# DMX-Card.net
KiCad netlist of a schematic drawn in EAGLE
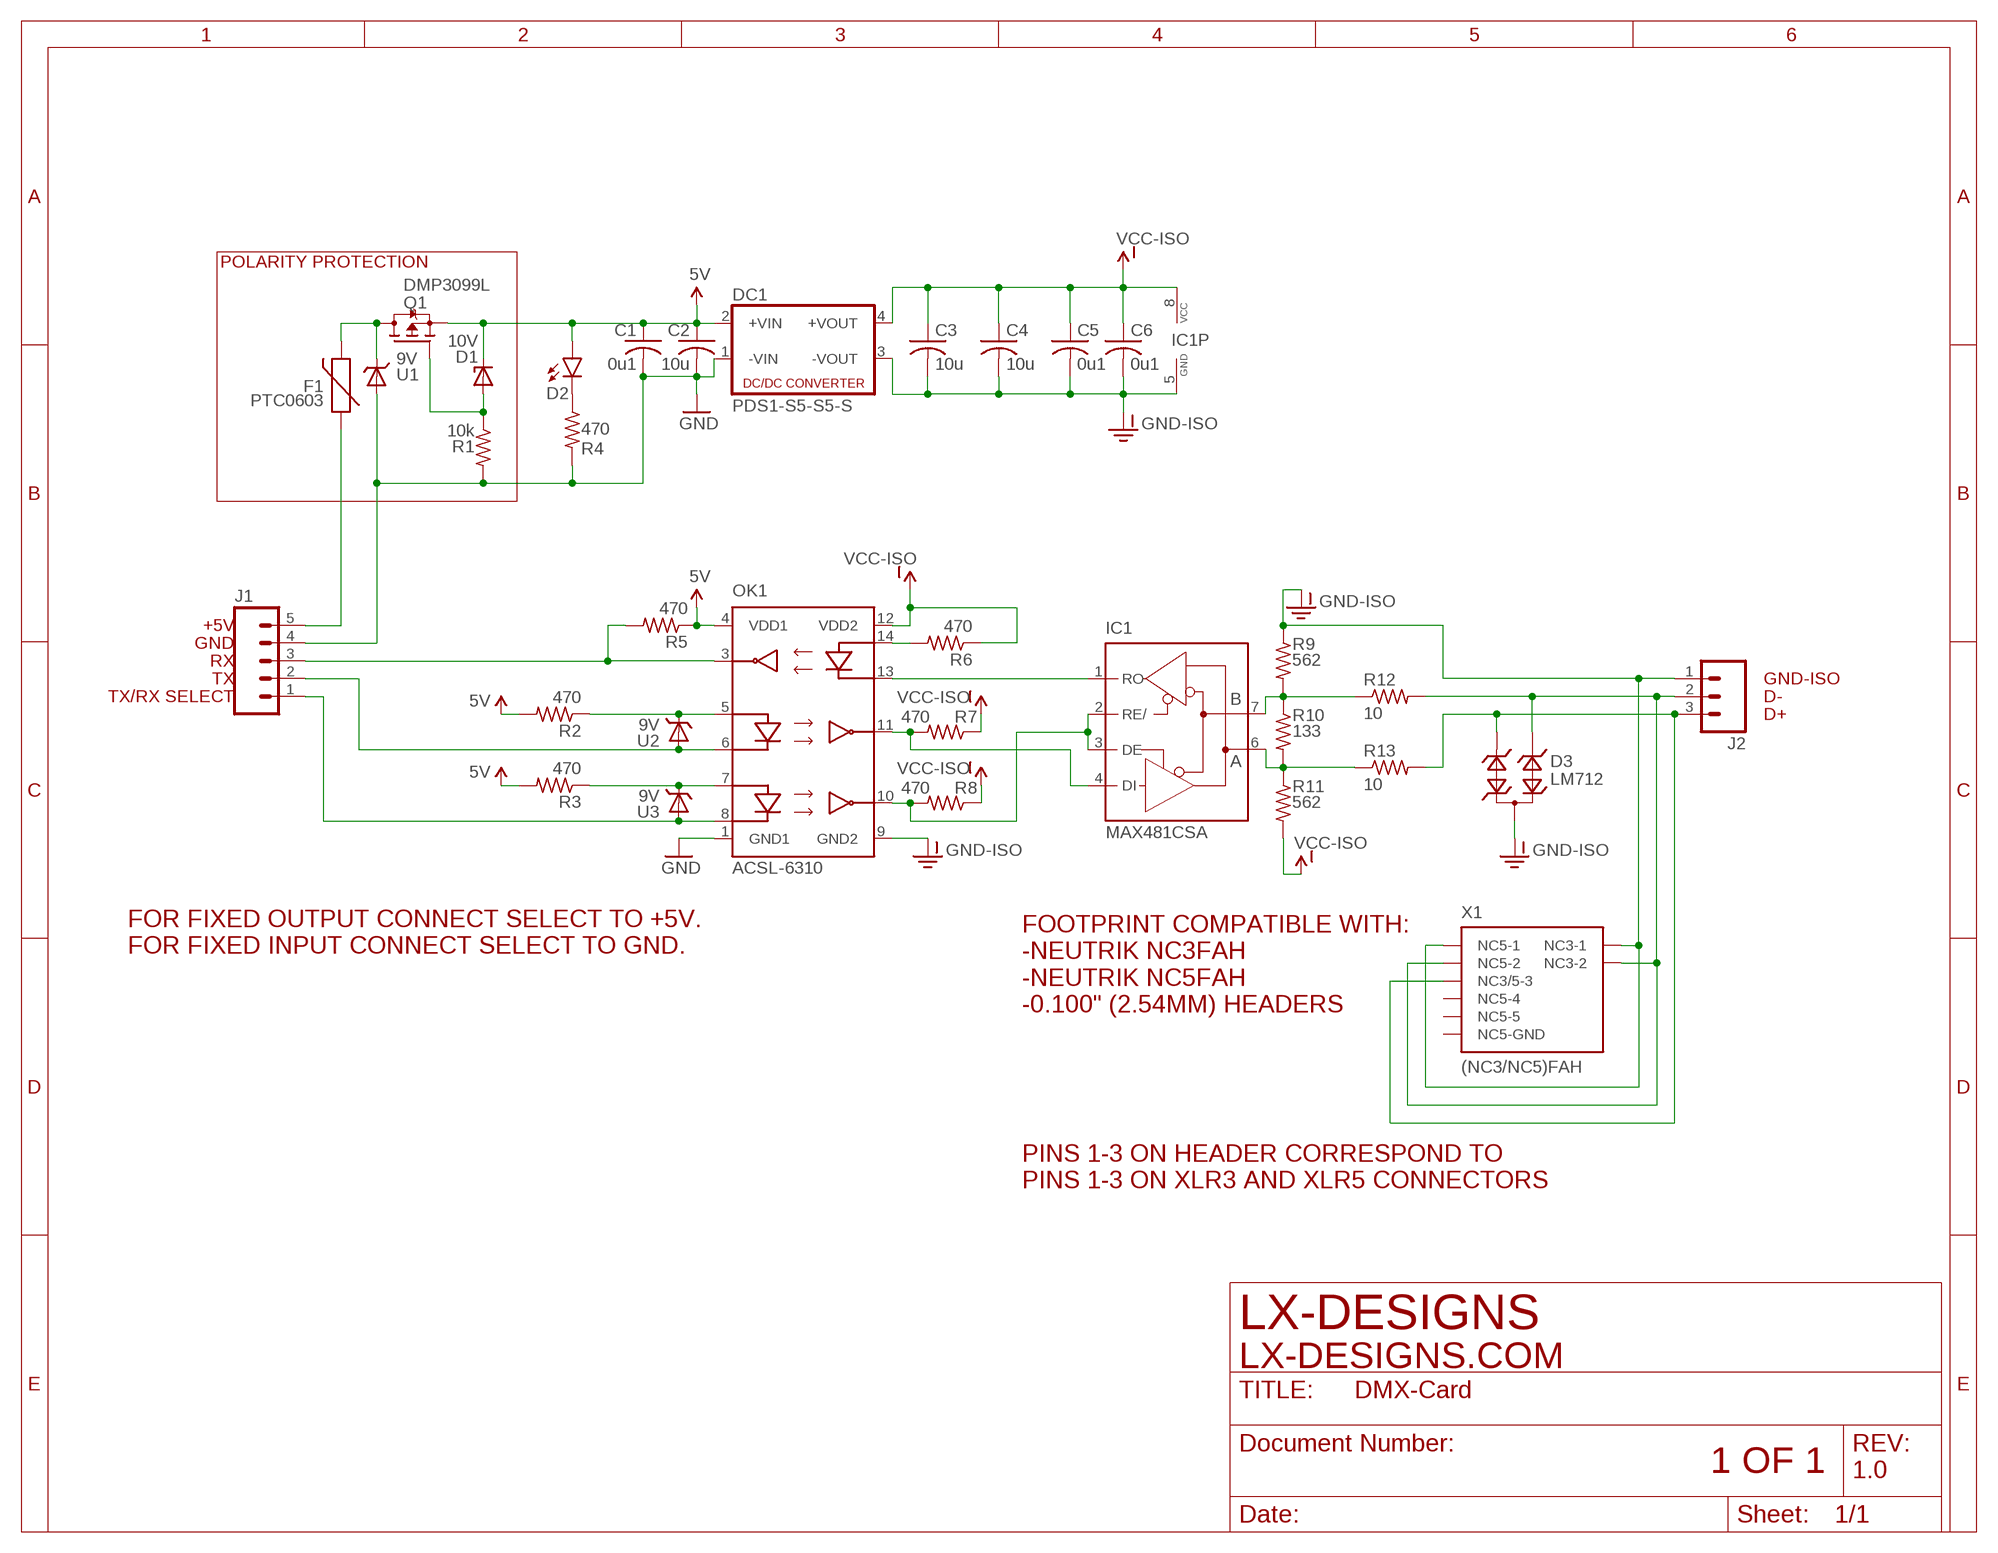
[diagram p0: schematic, sheet 1]

(export (version "E")
  (design (tool "Eeschema 10.0.6"))
  (components
    (comp (ref "C1")
      (value "0u1")
      (footprint "eagle-import:C0603K")
      (libsource (lib "eagle-import") (part "C-USC0603K"))
    )
    (comp (ref "C2")
      (value "10u")
      (footprint "eagle-import:C0603K")
      (libsource (lib "eagle-import") (part "C-USC0603K"))
    )
    (comp (ref "C3")
      (value "10u")
      (footprint "eagle-import:C0603K")
      (libsource (lib "eagle-import") (part "C-USC0603K"))
    )
    (comp (ref "C4")
      (value "10u")
      (footprint "eagle-import:C0603K")
      (libsource (lib "eagle-import") (part "C-USC0603K"))
    )
    (comp (ref "C5")
      (value "0u1")
      (footprint "eagle-import:C0603K")
      (libsource (lib "eagle-import") (part "C-USC0603K"))
    )
    (comp (ref "C6")
      (value "0u1")
      (footprint "eagle-import:C0603K")
      (libsource (lib "eagle-import") (part "C-USC0603K"))
    )
    (comp (ref "D1")
      (value "10V")
      (footprint "eagle-import:SOD323")
      (libsource (lib "eagle-import") (part "ZENER-DIODESOD-323"))
    )
    (comp (ref "D2")
      (value "LED0603")
      (footprint "eagle-import:LED-0603")
      (libsource (lib "eagle-import") (part "LED0603"))
    )
    (comp (ref "D3")
      (value "LM712")
      (footprint "eagle-import:SOT23")
      (libsource (lib "eagle-import") (part "CDSOT23-SM712SOT23-STANDARD"))
    )
    (comp (ref "DC1")
      (value "PDS1-S5-S5-S")
      (footprint "eagle-import:4SIL")
      (libsource (lib "eagle-import") (part "VA-?S0505"))
    )
    (comp (ref "F1")
      (value "PTC0603")
      (footprint "eagle-import:0603")
      (libsource (lib "eagle-import") (part "PTC0603"))
    )
    (comp (ref "IC1")
      (value "MAX481CSA")
      (footprint "eagle-import:SO08")
      (fields (field (name "MF") "MAXIM"))
      (libsource (lib "eagle-import") (part "MAX481CSA"))
    )
    (comp (ref "J1")
      (value "M05NO_SILK")
      (footprint "eagle-import:1X05_NO_SILK")
      (libsource (lib "eagle-import") (part "M05NO_SILK"))
    )
    (comp (ref "J2")
      (value "M031X03_NO_SILK")
      (footprint "eagle-import:1X03_NO_SILK")
      (libsource (lib "eagle-import") (part "M031X03_NO_SILK"))
    )
    (comp (ref "OK1")
      (value "ACSL-6310")
      (footprint "eagle-import:SO-16")
      (libsource (lib "eagle-import") (part "ACSL-60"))
    )
    (comp (ref "Q1")
      (value "DMP3099L")
      (footprint "eagle-import:SOT23")
      (libsource (lib "eagle-import") (part "BSA223SPSOT23"))
    )
    (comp (ref "R1")
      (value "10k")
      (footprint "eagle-import:R0603")
      (libsource (lib "eagle-import") (part "R-US_R0603"))
    )
    (comp (ref "R2")
      (value "470")
      (footprint "eagle-import:R0603")
      (libsource (lib "eagle-import") (part "R-US_R0603"))
    )
    (comp (ref "R3")
      (value "470")
      (footprint "eagle-import:R0603")
      (libsource (lib "eagle-import") (part "R-US_R0603"))
    )
    (comp (ref "R4")
      (value "470")
      (footprint "eagle-import:R0603")
      (libsource (lib "eagle-import") (part "R-US_R0603"))
    )
    (comp (ref "R5")
      (value "470")
      (footprint "eagle-import:R0603")
      (libsource (lib "eagle-import") (part "R-US_R0603"))
    )
    (comp (ref "R6")
      (value "470")
      (footprint "eagle-import:R0603")
      (libsource (lib "eagle-import") (part "R-US_R0603"))
    )
    (comp (ref "R7")
      (value "470")
      (footprint "eagle-import:R0603")
      (libsource (lib "eagle-import") (part "R-US_R0603"))
    )
    (comp (ref "R8")
      (value "470")
      (footprint "eagle-import:R0603")
      (libsource (lib "eagle-import") (part "R-US_R0603"))
    )
    (comp (ref "R9")
      (value "562")
      (footprint "eagle-import:R0603")
      (libsource (lib "eagle-import") (part "R-US_R0603"))
    )
    (comp (ref "R10")
      (value "133")
      (footprint "eagle-import:R0603")
      (libsource (lib "eagle-import") (part "R-US_R0603"))
    )
    (comp (ref "R11")
      (value "562")
      (footprint "eagle-import:R0603")
      (libsource (lib "eagle-import") (part "R-US_R0603"))
    )
    (comp (ref "R12")
      (value "10")
      (footprint "eagle-import:R0603")
      (libsource (lib "eagle-import") (part "R-US_R0603"))
    )
    (comp (ref "R13")
      (value "10")
      (footprint "eagle-import:R0603")
      (libsource (lib "eagle-import") (part "R-US_R0603"))
    )
    (comp (ref "U1")
      (value "9V")
      (footprint "eagle-import:SOD323-NOSILK")
      (libsource (lib "eagle-import") (part "TVS-DIODESOD323-NOSILK"))
    )
    (comp (ref "U2")
      (value "9V")
      (footprint "eagle-import:SOD323-NOSILK")
      (libsource (lib "eagle-import") (part "TVS-DIODESOD323-NOSILK"))
    )
    (comp (ref "U3")
      (value "9V")
      (footprint "eagle-import:SOD323-NOSILK")
      (libsource (lib "eagle-import") (part "TVS-DIODESOD323-NOSILK"))
    )
    (comp (ref "X1")
      (value "(NC3/NC5)FAH")
      (footprint "eagle-import:NC3FAH-NC5FAH-NOSILK")
      (libsource (lib "eagle-import") (part "CUSTOMNC3FAH-NC3MAH-NOSILK"))
    )
  )
  (nets
    (net (code "1") (name "5V") (class "Default")
      (node (ref "C1") (pin "1") (pinfunction "1_1") (pintype "passive"))
      (node (ref "C2") (pin "1") (pinfunction "1_1") (pintype "passive"))
      (node (ref "D1") (pin "C") (pinfunction "C_C") (pintype "passive"))
      (node (ref "D2") (pin "A") (pinfunction "A_A") (pintype "passive"))
      (node (ref "DC1") (pin "2") (pinfunction "+VIN_2") (pintype "passive"))
      (node (ref "OK1") (pin "4") (pinfunction "VDD1_4") (pintype "power_in"))
      (node (ref "Q1") (pin "2") (pinfunction "S_2") (pintype "passive"))
      (node (ref "R2") (pin "2") (pinfunction "2_2") (pintype "passive"))
      (node (ref "R3") (pin "2") (pinfunction "2_2") (pintype "passive"))
      (node (ref "R5") (pin "1") (pinfunction "1_1") (pintype "passive"))
    )
    (net (code "2") (name "GND") (class "Default")
      (node (ref "C1") (pin "2") (pinfunction "2_2") (pintype "passive"))
      (node (ref "C2") (pin "2") (pinfunction "2_2") (pintype "passive"))
      (node (ref "DC1") (pin "1") (pinfunction "-VIN_1") (pintype "passive"))
      (node (ref "J1") (pin "4") (pinfunction "4_4") (pintype "passive"))
      (node (ref "OK1") (pin "1") (pinfunction "GND1_1") (pintype "bidirectional"))
      (node (ref "R1") (pin "2") (pinfunction "2_2") (pintype "passive"))
      (node (ref "R4") (pin "2") (pinfunction "2_2") (pintype "passive"))
      (node (ref "U1") (pin "A") (pinfunction "A_A") (pintype "passive"))
    )
    (net (code "3") (name "GND-ISO") (class "Default")
      (node (ref "C3") (pin "2") (pinfunction "2_2") (pintype "passive"))
      (node (ref "C4") (pin "2") (pinfunction "2_2") (pintype "passive"))
      (node (ref "C5") (pin "2") (pinfunction "2_2") (pintype "passive"))
      (node (ref "C6") (pin "2") (pinfunction "2_2") (pintype "passive"))
      (node (ref "D3") (pin "3") (pinfunction "3_3") (pintype "passive"))
      (node (ref "DC1") (pin "3") (pinfunction "-VOUT_3") (pintype "passive"))
      (node (ref "IC1") (pin "5") (pinfunction "GND_5") (pintype "power_in"))
      (node (ref "J2") (pin "1") (pinfunction "1_1") (pintype "passive"))
      (node (ref "OK1") (pin "9") (pinfunction "GND2_9") (pintype "power_in"))
      (node (ref "R9") (pin "1") (pinfunction "1_1") (pintype "passive"))
      (node (ref "X1") (pin "NC3-1") (pinfunction "NC3-1_NC3-1") (pintype "bidirectional"))
      (node (ref "X1") (pin "NC5-1") (pinfunction "NC5-1_NC5-1") (pintype "bidirectional"))
    )
    (net (code "4") (name "Net-(D2-PadC)") (class "Default")
      (node (ref "D2") (pin "C") (pinfunction "C_C") (pintype "passive"))
      (node (ref "R4") (pin "1") (pinfunction "1_1") (pintype "passive"))
    )
    (net (code "5") (name "Net-(D3-Pad1)") (class "Default")
      (node (ref "D3") (pin "1") (pinfunction "1_1") (pintype "passive"))
      (node (ref "J2") (pin "2") (pinfunction "2_2") (pintype "passive"))
      (node (ref "R12") (pin "2") (pinfunction "2_2") (pintype "passive"))
      (node (ref "X1") (pin "NC3-2") (pinfunction "NC3-2_NC3-2") (pintype "bidirectional"))
      (node (ref "X1") (pin "NC5-2") (pinfunction "NC5-2_NC5-2") (pintype "bidirectional"))
    )
    (net (code "6") (name "Net-(F1-Pad1)") (class "Default")
      (node (ref "F1") (pin "1") (pinfunction "1_1") (pintype "bidirectional"))
      (node (ref "J1") (pin "5") (pinfunction "5_5") (pintype "passive"))
    )
    (net (code "7") (name "Net-(IC1A-A)") (class "Default")
      (node (ref "IC1") (pin "6") (pinfunction "A_6") (pintype "passive"))
      (node (ref "R10") (pin "2") (pinfunction "2_2") (pintype "passive"))
      (node (ref "R11") (pin "1") (pinfunction "1_1") (pintype "passive"))
      (node (ref "R13") (pin "1") (pinfunction "1_1") (pintype "passive"))
    )
    (net (code "8") (name "Net-(IC1A-B)") (class "Default")
      (node (ref "IC1") (pin "7") (pinfunction "B_7") (pintype "passive"))
      (node (ref "R10") (pin "1") (pinfunction "1_1") (pintype "passive"))
      (node (ref "R12") (pin "1") (pinfunction "1_1") (pintype "passive"))
      (node (ref "R9") (pin "2") (pinfunction "2_2") (pintype "passive"))
    )
    (net (code "9") (name "Net-(IC1A-DE)") (class "Default")
      (node (ref "IC1") (pin "2") (pinfunction "RE/_2") (pintype "input"))
      (node (ref "IC1") (pin "3") (pinfunction "DE_3") (pintype "input"))
      (node (ref "OK1") (pin "10") (pinfunction "VO2_10") (pintype "output"))
      (node (ref "R8") (pin "2") (pinfunction "2_2") (pintype "passive"))
    )
    (net (code "10") (name "Net-(IC1A-DI)") (class "Default")
      (node (ref "IC1") (pin "4") (pinfunction "DI_4") (pintype "input"))
      (node (ref "OK1") (pin "11") (pinfunction "VO1_11") (pintype "output"))
      (node (ref "R7") (pin "2") (pinfunction "2_2") (pintype "passive"))
    )
    (net (code "11") (name "Net-(IC1A-RO)") (class "Default")
      (node (ref "IC1") (pin "1") (pinfunction "RO_1") (pintype "output"))
      (node (ref "OK1") (pin "13") (pinfunction "C3_13") (pintype "output"))
    )
    (net (code "12") (name "Net-(OK1-A1)") (class "Default")
      (node (ref "OK1") (pin "5") (pinfunction "A1_5") (pintype "input"))
      (node (ref "R2") (pin "1") (pinfunction "1_1") (pintype "passive"))
      (node (ref "U2") (pin "C") (pinfunction "C_C") (pintype "passive"))
    )
    (net (code "13") (name "Net-(OK1-A2)") (class "Default")
      (node (ref "OK1") (pin "7") (pinfunction "A2_7") (pintype "input"))
      (node (ref "R3") (pin "1") (pinfunction "1_1") (pintype "passive"))
      (node (ref "U3") (pin "C") (pinfunction "C_C") (pintype "passive"))
    )
    (net (code "14") (name "Net-(OK1-A3)") (class "Default")
      (node (ref "OK1") (pin "14") (pinfunction "A3_14") (pintype "input"))
      (node (ref "R6") (pin "2") (pinfunction "2_2") (pintype "passive"))
    )
    (net (code "15") (name "Net-(OK1-C1)") (class "Default")
      (node (ref "J1") (pin "2") (pinfunction "2_2") (pintype "passive"))
      (node (ref "OK1") (pin "6") (pinfunction "C1_6") (pintype "output"))
      (node (ref "U2") (pin "A") (pinfunction "A_A") (pintype "passive"))
    )
    (net (code "16") (name "Net-(OK1-C2)") (class "Default")
      (node (ref "J1") (pin "1") (pinfunction "1_1") (pintype "passive"))
      (node (ref "OK1") (pin "8") (pinfunction "C2_8") (pintype "output"))
      (node (ref "U3") (pin "A") (pinfunction "A_A") (pintype "passive"))
    )
    (net (code "17") (name "Net-(OK1-V03)") (class "Default")
      (node (ref "J1") (pin "3") (pinfunction "3_3") (pintype "passive"))
      (node (ref "OK1") (pin "3") (pinfunction "V03_3") (pintype "output"))
      (node (ref "R5") (pin "2") (pinfunction "2_2") (pintype "passive"))
    )
    (net (code "18") (name "Net-(Q1-D)") (class "Default")
      (node (ref "F1") (pin "2") (pinfunction "2_2") (pintype "bidirectional"))
      (node (ref "Q1") (pin "3") (pinfunction "D_3") (pintype "passive"))
      (node (ref "U1") (pin "C") (pinfunction "C_C") (pintype "passive"))
    )
    (net (code "19") (name "Net-(Q1-G)") (class "Default")
      (node (ref "D1") (pin "A") (pinfunction "A_A") (pintype "passive"))
      (node (ref "Q1") (pin "1") (pinfunction "G_1") (pintype "passive"))
      (node (ref "R1") (pin "1") (pinfunction "1_1") (pintype "passive"))
    )
    (net (code "20") (name "Net-(X1-NC3{slash}5-3)") (class "Default")
      (node (ref "D3") (pin "2") (pinfunction "2_2") (pintype "passive"))
      (node (ref "J2") (pin "3") (pinfunction "3_3") (pintype "passive"))
      (node (ref "R13") (pin "2") (pinfunction "2_2") (pintype "passive"))
      (node (ref "X1") (pin "NC3-3") (pinfunction "NC3/5-3_NC3-3") (pintype "bidirectional"))
    )
    (net (code "21") (name "VCC-ISO") (class "Default")
      (node (ref "C3") (pin "1") (pinfunction "1_1") (pintype "passive"))
      (node (ref "C4") (pin "1") (pinfunction "1_1") (pintype "passive"))
      (node (ref "C5") (pin "1") (pinfunction "1_1") (pintype "passive"))
      (node (ref "C6") (pin "1") (pinfunction "1_1") (pintype "passive"))
      (node (ref "DC1") (pin "4") (pinfunction "+VOUT_4") (pintype "passive"))
      (node (ref "IC1") (pin "8") (pinfunction "VCC_8") (pintype "power_in"))
      (node (ref "OK1") (pin "12") (pinfunction "VDD2_12") (pintype "power_in"))
      (node (ref "R11") (pin "2") (pinfunction "2_2") (pintype "passive"))
      (node (ref "R6") (pin "1") (pinfunction "1_1") (pintype "passive"))
      (node (ref "R7") (pin "1") (pinfunction "1_1") (pintype "passive"))
      (node (ref "R8") (pin "1") (pinfunction "1_1") (pintype "passive"))
    )
    (net (code "22") (name "unconnected-(X1-NC5-GND-PadGND)") (class "Default")
      (node (ref "X1") (pin "GND") (pinfunction "NC5-GND_GND") (pintype "bidirectional"))
    )
    (net (code "23") (name "unconnected-(X1-PadNC5-4)") (class "Default")
      (node (ref "X1") (pin "NC5-4") (pinfunction "NC5-4_NC5-4") (pintype "bidirectional"))
    )
    (net (code "24") (name "unconnected-(X1-PadNC5-5)") (class "Default")
      (node (ref "X1") (pin "NC5-5") (pinfunction "NC5-5_NC5-5") (pintype "bidirectional"))
    )
  )
)
